# design.net
KiCad netlist of a schematic drawn in Altium Designer
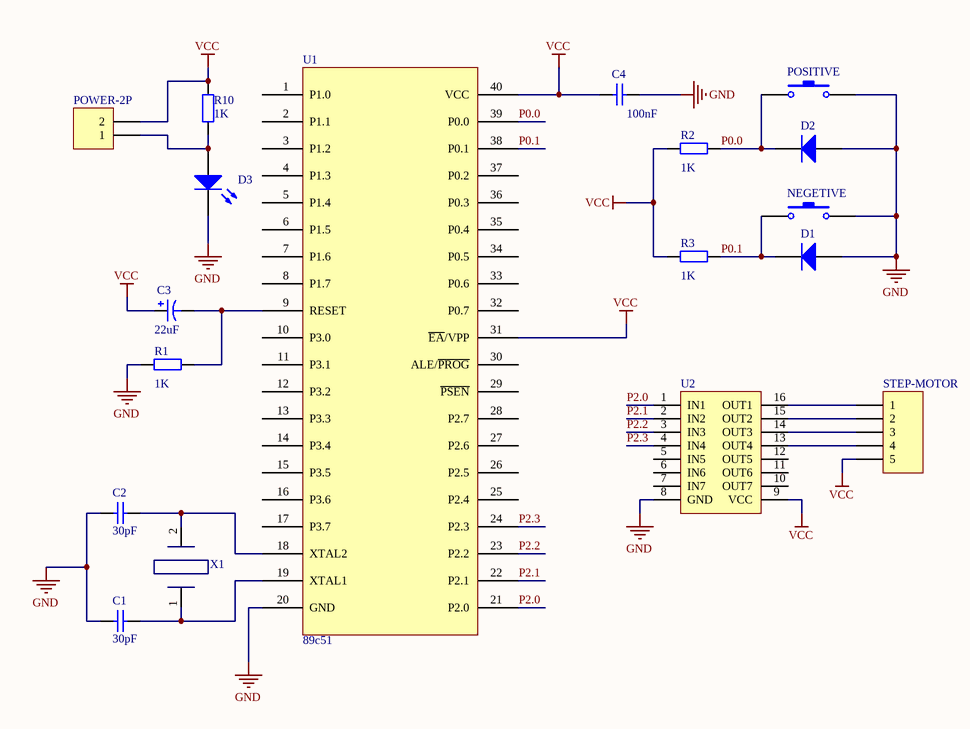
[diagram p0: 步进电机控制电路.SchDoc]

(export (version "E")
  (design (tool "Eeschema 10.0.6"))
  (components
    (comp (ref "C1")
      (value "30pF")
      (footprint "RAD-0.3")
      (description "Capacitor")
      (fields (field (name "Comment") "Cap") (field (name "PUBLISHER") "Altium Limited"))
      (libsource (lib "Miscellaneous Devices") (part "Cap"))
    )
    (comp (ref "C2")
      (value "30pF")
      (footprint "RAD-0.3")
      (description "Capacitor")
      (fields (field (name "Comment") "Cap") (field (name "PUBLISHER") "Altium Limited"))
      (libsource (lib "Miscellaneous Devices") (part "Cap"))
    )
    (comp (ref "C3")
      (value "22uF")
      (footprint "RB7.6-15")
      (description "Polarized Capacitor (Radial)")
      (fields (field (name "Comment") "Cap Pol1") (field (name "PUBLISHER") "Altium Limited"))
      (libsource (lib "Miscellaneous Devices") (part "Cap Pol1"))
    )
    (comp (ref "C4")
      (value "100nF")
      (footprint "RAD-0.3")
      (description "Capacitor")
      (fields (field (name "Comment") "Cap") (field (name "PUBLISHER") "Altium Limited"))
      (libsource (lib "Miscellaneous Devices") (part "Cap"))
    )
    (comp (ref "D1")
      (value "Diode 1N4148")
      (footprint "DO-35")
      (description "High Conductance Fast Diode")
      (fields (field (name "PUBLISHER") "Altium Limited"))
      (libsource (lib "Miscellaneous Devices") (part "Diode 1N4148"))
    )
    (comp (ref "D2")
      (value "Diode 1N4148")
      (footprint "DO-35")
      (description "High Conductance Fast Diode")
      (fields (field (name "PUBLISHER") "Altium Limited"))
      (libsource (lib "Miscellaneous Devices") (part "Diode 1N4148"))
    )
    (comp (ref "D3")
      (value "D3")
      (footprint "LED-0")
      (description "Typical INFRARED GaAs LED")
      (fields (field (name "PUBLISHER") "Altium Limited"))
      (libsource (lib "Miscellaneous Devices") (part "LED0"))
    )
    (comp (ref "NEGETIVE")
      (value "SW-PB")
      (footprint "SPST-2")
      (description "Switch")
      (fields (field (name "PUBLISHER") "Altium Limited"))
      (libsource (lib "Miscellaneous Devices") (part "SW-PB"))
    )
    (comp (ref "POSITIVE")
      (value "SW-PB")
      (footprint "SPST-2")
      (description "Switch")
      (fields (field (name "PUBLISHER") "Altium Limited"))
      (libsource (lib "Miscellaneous Devices") (part "SW-PB"))
    )
    (comp (ref "POWER-2P")
      (value "Header 2")
      (footprint "HDR1X2")
      (description "Header, 2-Pin")
      (fields (field (name "PUBLISHER") "Altium Limited"))
      (libsource (lib "Miscellaneous Connectors") (part "Header 2"))
    )
    (comp (ref "R1")
      (value "1K")
      (footprint "AXIAL-0.4")
      (description "Resistor")
      (fields (field (name "Comment") "Res2") (field (name "PUBLISHER") "Altium Limited"))
      (libsource (lib "Miscellaneous Devices") (part "Res2"))
    )
    (comp (ref "R2")
      (value "1K")
      (footprint "AXIAL-0.4")
      (description "Resistor")
      (fields (field (name "Comment") "Res2") (field (name "PUBLISHER") "Altium Limited"))
      (libsource (lib "Miscellaneous Devices") (part "Res2"))
    )
    (comp (ref "R3")
      (value "1K")
      (footprint "AXIAL-0.4")
      (description "Resistor")
      (fields (field (name "Comment") "Res2") (field (name "PUBLISHER") "Altium Limited"))
      (libsource (lib "Miscellaneous Devices") (part "Res2"))
    )
    (comp (ref "R10")
      (value "1K")
      (footprint "AXIAL-0.4")
      (description "Resistor")
      (fields (field (name "Comment") "Res2") (field (name "PUBLISHER") "Altium Limited"))
      (libsource (lib "") (part "Res2_1"))
    )
    (comp (ref "STEP-MOTOR")
      (value "Header 5")
      (footprint "HDR1X5")
      (description "Header, 5-Pin")
      (fields (field (name "PUBLISHER") "Altium Limited"))
      (libsource (lib "Miscellaneous Connectors") (part "Header 5"))
    )
    (comp (ref "U1") (value "89c51") (footprint "89c51") (libsource (lib "89c51") (part "Component_1")))
    (comp (ref "U2")
      (value "Component_1")
      (footprint "ULN2003")
      (libsource (lib "ULN2003") (part "Component_1"))
    )
    (comp (ref "X1")
      (value "Component_1")
      (footprint "LC-HC-49S")
      (libsource (lib "晶振") (part "Component_1"))
    )
  )
  (nets
    (net (code "1") (name "/P0.0") (class "Default")
      (node (ref "D2") (pin "2") (pinfunction "K_2") (pintype "passive"))
      (node (ref "POSITIVE") (pin "1") (pinfunction "1_1") (pintype "passive"))
      (node (ref "R2") (pin "2") (pinfunction "2_2") (pintype "passive"))
      (node (ref "U1") (pin "39") (pinfunction "P0.0_39") (pintype "passive"))
    )
    (net (code "2") (name "/P0.1") (class "Default")
      (node (ref "D1") (pin "2") (pinfunction "K_2") (pintype "passive"))
      (node (ref "NEGETIVE") (pin "1") (pinfunction "1_1") (pintype "passive"))
      (node (ref "R3") (pin "2") (pinfunction "2_2") (pintype "passive"))
      (node (ref "U1") (pin "38") (pinfunction "P0.1_38") (pintype "passive"))
    )
    (net (code "3") (name "/P2.0") (class "Default")
      (node (ref "U1") (pin "21") (pinfunction "P2.0_21") (pintype "passive"))
      (node (ref "U2") (pin "1") (pinfunction "IN1_1") (pintype "passive"))
    )
    (net (code "4") (name "/P2.1") (class "Default")
      (node (ref "U1") (pin "22") (pinfunction "P2.1_22") (pintype "passive"))
      (node (ref "U2") (pin "2") (pinfunction "IN2_2") (pintype "passive"))
    )
    (net (code "5") (name "/P2.2") (class "Default")
      (node (ref "U1") (pin "23") (pinfunction "P2.2_23") (pintype "passive"))
      (node (ref "U2") (pin "3") (pinfunction "IN3_3") (pintype "passive"))
    )
    (net (code "6") (name "/P2.3") (class "Default")
      (node (ref "U1") (pin "24") (pinfunction "P2.3_24") (pintype "passive"))
      (node (ref "U2") (pin "4") (pinfunction "IN4_4") (pintype "passive"))
    )
    (net (code "7") (name "GND") (class "Default")
      (node (ref "C1") (pin "2") (pinfunction "2_2") (pintype "passive"))
      (node (ref "C2") (pin "2") (pinfunction "2_2") (pintype "passive"))
      (node (ref "C4") (pin "2") (pinfunction "2_2") (pintype "passive"))
      (node (ref "D1") (pin "1") (pinfunction "A_1") (pintype "passive"))
      (node (ref "D2") (pin "1") (pinfunction "A_1") (pintype "passive"))
      (node (ref "D3") (pin "2") (pinfunction "K_2") (pintype "passive"))
      (node (ref "NEGETIVE") (pin "2") (pinfunction "2_2") (pintype "passive"))
      (node (ref "POSITIVE") (pin "2") (pinfunction "2_2") (pintype "passive"))
      (node (ref "R1") (pin "1") (pinfunction "1_1") (pintype "passive"))
      (node (ref "U1") (pin "20") (pinfunction "GND_20") (pintype "passive"))
      (node (ref "U2") (pin "8") (pinfunction "GND_8") (pintype "passive"))
    )
    (net (code "8") (name "Net-(D3-A)") (class "Default")
      (node (ref "D3") (pin "1") (pinfunction "A_1") (pintype "passive"))
      (node (ref "POWER-2P") (pin "1") (pinfunction "1_1") (pintype "passive"))
      (node (ref "R10") (pin "1") (pinfunction "1_1") (pintype "passive"))
    )
    (net (code "9") (name "Net-(U1-RESET)") (class "Default")
      (node (ref "C3") (pin "2") (pinfunction "2_2") (pintype "passive"))
      (node (ref "R1") (pin "2") (pinfunction "2_2") (pintype "passive"))
      (node (ref "U1") (pin "9") (pinfunction "RESET_9") (pintype "passive"))
    )
    (net (code "10") (name "Net-(U1-XTAL1)") (class "Default")
      (node (ref "C1") (pin "1") (pinfunction "1_1") (pintype "passive"))
      (node (ref "U1") (pin "19") (pinfunction "XTAL1_19") (pintype "passive"))
      (node (ref "X1") (pin "1") (pinfunction "1_1") (pintype "passive"))
    )
    (net (code "11") (name "Net-(U1-XTAL2)") (class "Default")
      (node (ref "C2") (pin "1") (pinfunction "1_1") (pintype "passive"))
      (node (ref "U1") (pin "18") (pinfunction "XTAL2_18") (pintype "passive"))
      (node (ref "X1") (pin "2") (pinfunction "2_2") (pintype "passive"))
    )
    (net (code "12") (name "Net-(U2-OUT1)") (class "Default")
      (node (ref "STEP-MOTOR") (pin "1") (pinfunction "1_1") (pintype "passive"))
      (node (ref "U2") (pin "16") (pinfunction "OUT1_16") (pintype "passive"))
    )
    (net (code "13") (name "Net-(U2-OUT2)") (class "Default")
      (node (ref "STEP-MOTOR") (pin "2") (pinfunction "2_2") (pintype "passive"))
      (node (ref "U2") (pin "15") (pinfunction "OUT2_15") (pintype "passive"))
    )
    (net (code "14") (name "Net-(U2-OUT3)") (class "Default")
      (node (ref "STEP-MOTOR") (pin "3") (pinfunction "3_3") (pintype "passive"))
      (node (ref "U2") (pin "14") (pinfunction "OUT3_14") (pintype "passive"))
    )
    (net (code "15") (name "Net-(U2-OUT4)") (class "Default")
      (node (ref "STEP-MOTOR") (pin "4") (pinfunction "4_4") (pintype "passive"))
      (node (ref "U2") (pin "13") (pinfunction "OUT4_13") (pintype "passive"))
    )
    (net (code "16") (name "VCC") (class "Default")
      (node (ref "C3") (pin "1") (pinfunction "1_1") (pintype "passive"))
      (node (ref "C4") (pin "1") (pinfunction "1_1") (pintype "passive"))
      (node (ref "POWER-2P") (pin "2") (pinfunction "2_2") (pintype "passive"))
      (node (ref "R10") (pin "2") (pinfunction "2_2") (pintype "passive"))
      (node (ref "R2") (pin "1") (pinfunction "1_1") (pintype "passive"))
      (node (ref "R3") (pin "1") (pinfunction "1_1") (pintype "passive"))
      (node (ref "STEP-MOTOR") (pin "5") (pinfunction "5_5") (pintype "passive"))
      (node (ref "U1") (pin "31") (pinfunction "~{EA}/VPP_31") (pintype "passive"))
      (node (ref "U1") (pin "40") (pinfunction "VCC_40") (pintype "passive"))
      (node (ref "U2") (pin "9") (pinfunction "VCC_9") (pintype "passive"))
    )
    (net (code "17") (name "unconnected-(U1-ALE{slash}~{PROG}-Pad30)") (class "Default")
      (node (ref "U1") (pin "30") (pinfunction "ALE/~{PROG}_30") (pintype "passive"))
    )
    (net (code "18") (name "unconnected-(U1-P0.2-Pad37)") (class "Default")
      (node (ref "U1") (pin "37") (pinfunction "P0.2_37") (pintype "passive"))
    )
    (net (code "19") (name "unconnected-(U1-P0.3-Pad36)") (class "Default")
      (node (ref "U1") (pin "36") (pinfunction "P0.3_36") (pintype "passive"))
    )
    (net (code "20") (name "unconnected-(U1-P0.4-Pad35)") (class "Default")
      (node (ref "U1") (pin "35") (pinfunction "P0.4_35") (pintype "passive"))
    )
    (net (code "21") (name "unconnected-(U1-P0.5-Pad34)") (class "Default")
      (node (ref "U1") (pin "34") (pinfunction "P0.5_34") (pintype "passive"))
    )
    (net (code "22") (name "unconnected-(U1-P0.6-Pad33)") (class "Default")
      (node (ref "U1") (pin "33") (pinfunction "P0.6_33") (pintype "passive"))
    )
    (net (code "23") (name "unconnected-(U1-P0.7-Pad32)") (class "Default")
      (node (ref "U1") (pin "32") (pinfunction "P0.7_32") (pintype "passive"))
    )
    (net (code "24") (name "unconnected-(U1-P1.0-Pad1)") (class "Default")
      (node (ref "U1") (pin "1") (pinfunction "P1.0_1") (pintype "passive"))
    )
    (net (code "25") (name "unconnected-(U1-P1.1-Pad2)") (class "Default")
      (node (ref "U1") (pin "2") (pinfunction "P1.1_2") (pintype "passive"))
    )
    (net (code "26") (name "unconnected-(U1-P1.2-Pad3)") (class "Default")
      (node (ref "U1") (pin "3") (pinfunction "P1.2_3") (pintype "passive"))
    )
    (net (code "27") (name "unconnected-(U1-P1.3-Pad4)") (class "Default")
      (node (ref "U1") (pin "4") (pinfunction "P1.3_4") (pintype "passive"))
    )
    (net (code "28") (name "unconnected-(U1-P1.4-Pad5)") (class "Default")
      (node (ref "U1") (pin "5") (pinfunction "P1.4_5") (pintype "passive"))
    )
    (net (code "29") (name "unconnected-(U1-P1.5-Pad6)") (class "Default")
      (node (ref "U1") (pin "6") (pinfunction "P1.5_6") (pintype "passive"))
    )
    (net (code "30") (name "unconnected-(U1-P1.6-Pad7)") (class "Default")
      (node (ref "U1") (pin "7") (pinfunction "P1.6_7") (pintype "passive"))
    )
    (net (code "31") (name "unconnected-(U1-P1.7-Pad8)") (class "Default")
      (node (ref "U1") (pin "8") (pinfunction "P1.7_8") (pintype "passive"))
    )
    (net (code "32") (name "unconnected-(U1-P2.4-Pad25)") (class "Default")
      (node (ref "U1") (pin "25") (pinfunction "P2.4_25") (pintype "passive"))
    )
    (net (code "33") (name "unconnected-(U1-P2.5-Pad26)") (class "Default")
      (node (ref "U1") (pin "26") (pinfunction "P2.5_26") (pintype "passive"))
    )
    (net (code "34") (name "unconnected-(U1-P2.6-Pad27)") (class "Default")
      (node (ref "U1") (pin "27") (pinfunction "P2.6_27") (pintype "passive"))
    )
    (net (code "35") (name "unconnected-(U1-P2.7-Pad28)") (class "Default")
      (node (ref "U1") (pin "28") (pinfunction "P2.7_28") (pintype "passive"))
    )
    (net (code "36") (name "unconnected-(U1-P3.0-Pad10)") (class "Default")
      (node (ref "U1") (pin "10") (pinfunction "P3.0_10") (pintype "passive"))
    )
    (net (code "37") (name "unconnected-(U1-P3.1-Pad11)") (class "Default")
      (node (ref "U1") (pin "11") (pinfunction "P3.1_11") (pintype "passive"))
    )
    (net (code "38") (name "unconnected-(U1-P3.2-Pad12)") (class "Default")
      (node (ref "U1") (pin "12") (pinfunction "P3.2_12") (pintype "passive"))
    )
    (net (code "39") (name "unconnected-(U1-P3.3-Pad13)") (class "Default")
      (node (ref "U1") (pin "13") (pinfunction "P3.3_13") (pintype "passive"))
    )
    (net (code "40") (name "unconnected-(U1-P3.4-Pad14)") (class "Default")
      (node (ref "U1") (pin "14") (pinfunction "P3.4_14") (pintype "passive"))
    )
    (net (code "41") (name "unconnected-(U1-P3.5-Pad15)") (class "Default")
      (node (ref "U1") (pin "15") (pinfunction "P3.5_15") (pintype "passive"))
    )
    (net (code "42") (name "unconnected-(U1-P3.6-Pad16)") (class "Default")
      (node (ref "U1") (pin "16") (pinfunction "P3.6_16") (pintype "passive"))
    )
    (net (code "43") (name "unconnected-(U1-P3.7-Pad17)") (class "Default")
      (node (ref "U1") (pin "17") (pinfunction "P3.7_17") (pintype "passive"))
    )
    (net (code "44") (name "unconnected-(U1-~{PSEN}-Pad29)") (class "Default")
      (node (ref "U1") (pin "29") (pinfunction "~{PSEN}_29") (pintype "passive"))
    )
    (net (code "45") (name "unconnected-(U2-IN5-Pad5)") (class "Default")
      (node (ref "U2") (pin "5") (pinfunction "IN5_5") (pintype "passive"))
    )
    (net (code "46") (name "unconnected-(U2-IN6-Pad6)") (class "Default")
      (node (ref "U2") (pin "6") (pinfunction "IN6_6") (pintype "passive"))
    )
    (net (code "47") (name "unconnected-(U2-IN7-Pad7)") (class "Default")
      (node (ref "U2") (pin "7") (pinfunction "IN7_7") (pintype "passive"))
    )
    (net (code "48") (name "unconnected-(U2-OUT5-Pad12)") (class "Default")
      (node (ref "U2") (pin "12") (pinfunction "OUT5_12") (pintype "passive"))
    )
    (net (code "49") (name "unconnected-(U2-OUT6-Pad11)") (class "Default")
      (node (ref "U2") (pin "11") (pinfunction "OUT6_11") (pintype "passive"))
    )
    (net (code "50") (name "unconnected-(U2-OUT7-Pad10)") (class "Default")
      (node (ref "U2") (pin "10") (pinfunction "OUT7_10") (pintype "passive"))
    )
  )
)
